# LSM303.net
KiCad netlist of a schematic drawn in Altium Designer
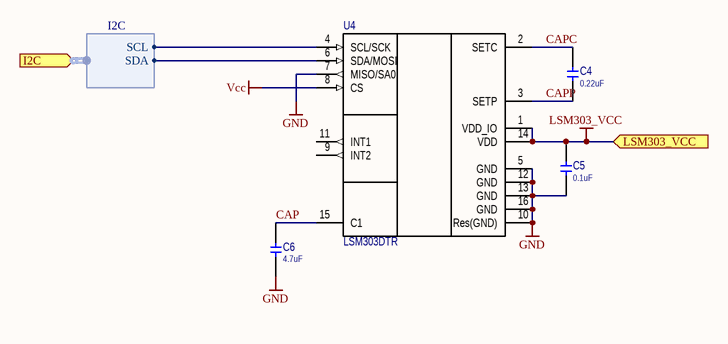
[diagram p0: LSM303.SchDoc]

(export (version "E")
  (design (tool "Eeschema 10.0.6"))
  (components
    (comp (ref "C4")
      (value "0.22uF")
      (footprint "CERCAP 0402")
      (description "Capacitor")
      (fields (field (name "Comment") "CERCAP 0402 0.22uF * X7R"))
      (libsource (lib "!main") (part "!Capacitor"))
    )
    (comp (ref "C5")
      (value "0.1uF")
      (footprint "CERCAP 0402")
      (description "Capacitor")
      (fields (field (name "Comment") "CERCAP 0402 0.1uF * X7R"))
      (libsource (lib "!main") (part "!Capacitor"))
    )
    (comp (ref "C6")
      (value "4.7uF")
      (footprint "CERCAP 0603")
      (description "Capacitor")
      (fields (field (name "Comment") "CERCAP 0603 4.7uF * X7R"))
      (libsource (lib "!main") (part "!Capacitor"))
    )
    (comp (ref "U4")
      (value "LSM303DTR")
      (footprint "LGA16_LSM303DTR")
      (description "Acc/Mag")
      (libsource (lib "sensors") (part "LSM303DTR"))
    )
  )
  (nets
    (net (code "3") (name "/CAP") (class "Default")
      (node (ref "C6") (pin "2") (pintype "passive"))
      (node (ref "U4") (pin "15") (pinfunction "C1_15") (pintype "power_in"))
    )
    (net (code "5") (name "/CAPC") (class "Default")
      (node (ref "C4") (pin "2") (pintype "passive"))
      (node (ref "U4") (pin "2") (pinfunction "SETC_2") (pintype "power_in"))
    )
    (net (code "6") (name "/CAPP") (class "Default")
      (node (ref "C4") (pin "1") (pintype "passive"))
      (node (ref "U4") (pin "3") (pinfunction "SETP_3") (pintype "power_in"))
    )
    (net (code "8") (name "/SCL") (class "Default")
      (node (ref "U4") (pin "4") (pinfunction "SCL/SCK_4") (pintype "input"))
    )
    (net (code "9") (name "/SDA") (class "Default")
      (node (ref "U4") (pin "6") (pinfunction "SDA/MOSI_6") (pintype "input"))
    )
    (net (code "10") (name "GND") (class "Default")
      (node (ref "C5") (pin "1") (pintype "passive"))
      (node (ref "C6") (pin "1") (pintype "passive"))
      (node (ref "U4") (pin "10") (pinfunction "Res(GND)_10") (pintype "power_in"))
      (node (ref "U4") (pin "12") (pinfunction "GND_12") (pintype "power_in"))
      (node (ref "U4") (pin "13") (pinfunction "GND_13") (pintype "power_in"))
      (node (ref "U4") (pin "16") (pinfunction "GND_16") (pintype "power_in"))
      (node (ref "U4") (pin "5") (pinfunction "GND_5") (pintype "power_in"))
      (node (ref "U4") (pin "7") (pinfunction "MISO/SA0_7") (pintype "output"))
    )
    (net (code "11") (name "LSM303_VCC") (class "Default")
      (node (ref "C5") (pin "2") (pintype "passive"))
      (node (ref "U4") (pin "1") (pinfunction "VDD_IO_1") (pintype "power_in"))
      (node (ref "U4") (pin "14") (pinfunction "VDD_14") (pintype "power_in"))
    )
    (net (code "12") (name "Vcc") (class "Default")
      (node (ref "U4") (pin "8") (pinfunction "CS_8") (pintype "input"))
    )
    (net (code "13") (name "unconnected-(U4-INT1-Pad11)") (class "Default")
      (node (ref "U4") (pin "11") (pinfunction "INT1_11") (pintype "output"))
    )
    (net (code "14") (name "unconnected-(U4-INT2-Pad9)") (class "Default")
      (node (ref "U4") (pin "9") (pinfunction "INT2_9") (pintype "output"))
    )
  )
)
